# LEDDisp8.net
KiCad netlist of a schematic drawn in EAGLE
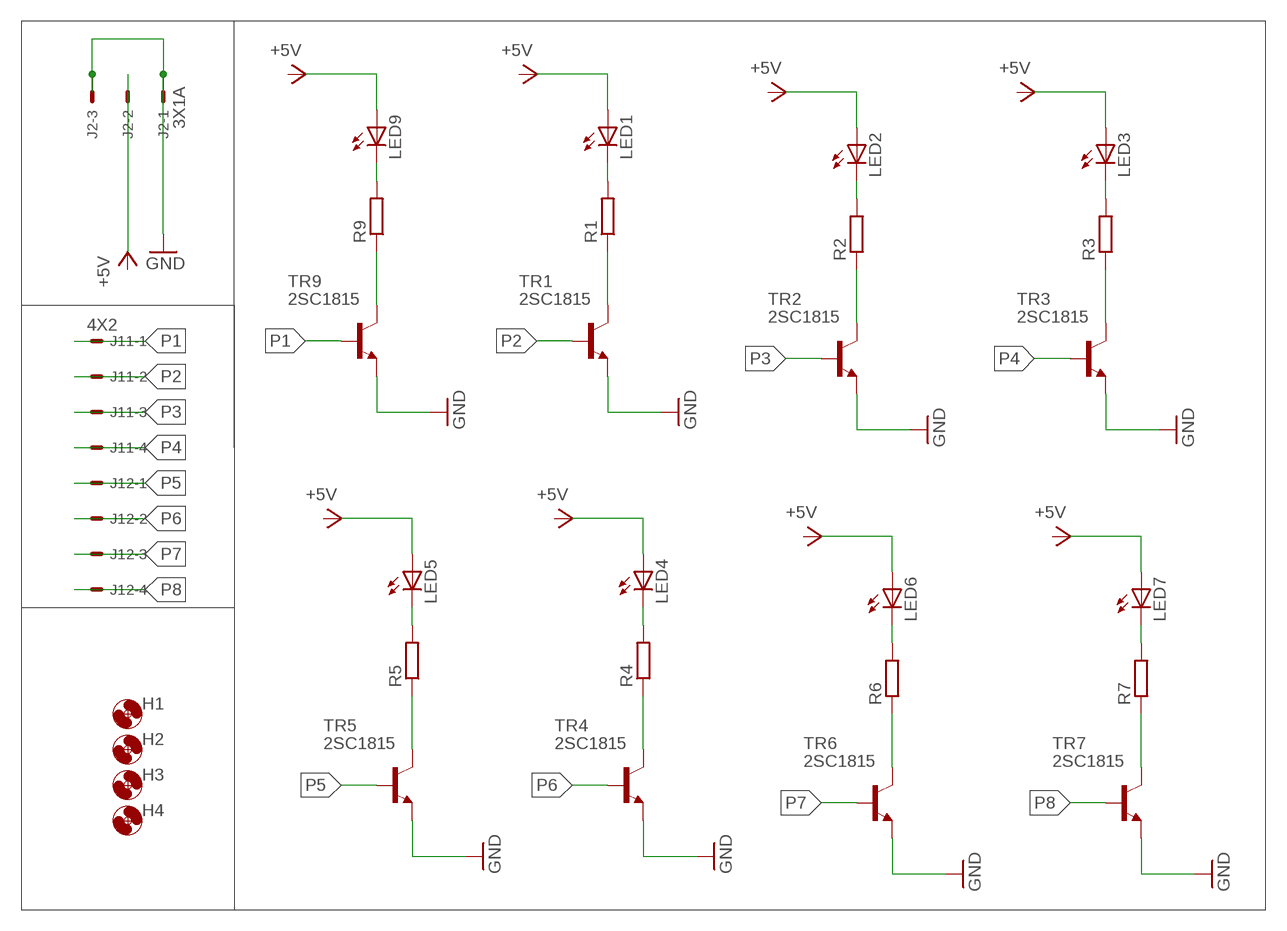
[diagram p0: schematic, sheet 1]

(export (version "E")
  (design (tool "Eeschema 10.0.6"))
  (components
    (comp (ref "H1")
      (value "HOLE3.3M3BOLT")
      (footprint "eagle-import:HOLE3.3")
      (libsource (lib "eagle-import") (part "HOLE3.3M3BOLT"))
    )
    (comp (ref "H2")
      (value "HOLE3.3M3BOLT")
      (footprint "eagle-import:HOLE3.3")
      (libsource (lib "eagle-import") (part "HOLE3.3M3BOLT"))
    )
    (comp (ref "H3")
      (value "HOLE3.3M3BOLT")
      (footprint "eagle-import:HOLE3.3")
      (libsource (lib "eagle-import") (part "HOLE3.3M3BOLT"))
    )
    (comp (ref "H4")
      (value "HOLE3.3M3BOLT")
      (footprint "eagle-import:HOLE3.3")
      (libsource (lib "eagle-import") (part "HOLE3.3M3BOLT"))
    )
    (comp (ref "J1")
      (value "4X2")
      (footprint "eagle-import:37208-62A3-004")
      (libsource (lib "eagle-import") (part "4X2"))
    )
    (comp (ref "J2")
      (value "3X1A")
      (footprint "eagle-import:37203-62A3-003")
      (libsource (lib "eagle-import") (part "3X1A"))
    )
    (comp (ref "LED1")
      (value "LED3MM")
      (footprint "eagle-import:LED3MM")
      (libsource (lib "eagle-import") (part "LED3MM"))
    )
    (comp (ref "LED2")
      (value "LED3MM")
      (footprint "eagle-import:LED3MM")
      (libsource (lib "eagle-import") (part "LED3MM"))
    )
    (comp (ref "LED3")
      (value "LED3MM")
      (footprint "eagle-import:LED3MM")
      (libsource (lib "eagle-import") (part "LED3MM"))
    )
    (comp (ref "LED4")
      (value "LED3MM")
      (footprint "eagle-import:LED3MM")
      (libsource (lib "eagle-import") (part "LED3MM"))
    )
    (comp (ref "LED5")
      (value "LED3MM")
      (footprint "eagle-import:LED3MM")
      (libsource (lib "eagle-import") (part "LED3MM"))
    )
    (comp (ref "LED6")
      (value "LED3MM")
      (footprint "eagle-import:LED3MM")
      (libsource (lib "eagle-import") (part "LED3MM"))
    )
    (comp (ref "LED7")
      (value "LED3MM")
      (footprint "eagle-import:LED3MM")
      (libsource (lib "eagle-import") (part "LED3MM"))
    )
    (comp (ref "LED9")
      (value "LED3MM")
      (footprint "eagle-import:LED3MM")
      (libsource (lib "eagle-import") (part "LED3MM"))
    )
    (comp (ref "R1")
      (value "R-EU_R3216W")
      (footprint "eagle-import:R3216W")
      (libsource (lib "eagle-import") (part "R-EU_R3216W"))
    )
    (comp (ref "R2")
      (value "R-EU_R3216W")
      (footprint "eagle-import:R3216W")
      (libsource (lib "eagle-import") (part "R-EU_R3216W"))
    )
    (comp (ref "R3")
      (value "R-EU_R3216W")
      (footprint "eagle-import:R3216W")
      (libsource (lib "eagle-import") (part "R-EU_R3216W"))
    )
    (comp (ref "R4")
      (value "R-EU_R3216W")
      (footprint "eagle-import:R3216W")
      (libsource (lib "eagle-import") (part "R-EU_R3216W"))
    )
    (comp (ref "R5")
      (value "R-EU_R3216W")
      (footprint "eagle-import:R3216W")
      (libsource (lib "eagle-import") (part "R-EU_R3216W"))
    )
    (comp (ref "R6")
      (value "R-EU_R3216W")
      (footprint "eagle-import:R3216W")
      (libsource (lib "eagle-import") (part "R-EU_R3216W"))
    )
    (comp (ref "R7")
      (value "R-EU_R3216W")
      (footprint "eagle-import:R3216W")
      (libsource (lib "eagle-import") (part "R-EU_R3216W"))
    )
    (comp (ref "R9")
      (value "R-EU_R3216W")
      (footprint "eagle-import:R3216W")
      (libsource (lib "eagle-import") (part "R-EU_R3216W"))
    )
    (comp (ref "TR1")
      (value "2SC1815")
      (footprint "eagle-import:TO92-")
      (libsource (lib "eagle-import") (part "2SC1815"))
    )
    (comp (ref "TR2")
      (value "2SC1815")
      (footprint "eagle-import:TO92-")
      (libsource (lib "eagle-import") (part "2SC1815"))
    )
    (comp (ref "TR3")
      (value "2SC1815")
      (footprint "eagle-import:TO92-")
      (libsource (lib "eagle-import") (part "2SC1815"))
    )
    (comp (ref "TR4")
      (value "2SC1815")
      (footprint "eagle-import:TO92-")
      (libsource (lib "eagle-import") (part "2SC1815"))
    )
    (comp (ref "TR5")
      (value "2SC1815")
      (footprint "eagle-import:TO92-")
      (libsource (lib "eagle-import") (part "2SC1815"))
    )
    (comp (ref "TR6")
      (value "2SC1815")
      (footprint "eagle-import:TO92-")
      (libsource (lib "eagle-import") (part "2SC1815"))
    )
    (comp (ref "TR7")
      (value "2SC1815")
      (footprint "eagle-import:TO92-")
      (libsource (lib "eagle-import") (part "2SC1815"))
    )
    (comp (ref "TR9")
      (value "2SC1815")
      (footprint "eagle-import:TO92-")
      (libsource (lib "eagle-import") (part "2SC1815"))
    )
  )
  (nets
    (net (code "2") (name "GND") (class "Default")
      (node (ref "J2") (pin "1-1") (pinfunction "S_1-1") (pintype "passive"))
      (node (ref "J2") (pin "1-3") (pinfunction "S_1-3") (pintype "passive"))
      (node (ref "TR1") (pin "E") (pinfunction "E_E") (pintype "passive"))
      (node (ref "TR2") (pin "E") (pinfunction "E_E") (pintype "passive"))
      (node (ref "TR3") (pin "E") (pinfunction "E_E") (pintype "passive"))
      (node (ref "TR4") (pin "E") (pinfunction "E_E") (pintype "passive"))
      (node (ref "TR5") (pin "E") (pinfunction "E_E") (pintype "passive"))
      (node (ref "TR6") (pin "E") (pinfunction "E_E") (pintype "passive"))
      (node (ref "TR7") (pin "E") (pinfunction "E_E") (pintype "passive"))
      (node (ref "TR9") (pin "E") (pinfunction "E_E") (pintype "passive"))
    )
    (net (code "3") (name "Net-(LED1-C)") (class "Default")
      (node (ref "LED1") (pin "K") (pinfunction "C_K") (pintype "passive"))
      (node (ref "R1") (pin "2") (pinfunction "2_2") (pintype "passive"))
    )
    (net (code "4") (name "Net-(LED2-C)") (class "Default")
      (node (ref "LED2") (pin "K") (pinfunction "C_K") (pintype "passive"))
      (node (ref "R2") (pin "2") (pinfunction "2_2") (pintype "passive"))
    )
    (net (code "5") (name "Net-(LED3-C)") (class "Default")
      (node (ref "LED3") (pin "K") (pinfunction "C_K") (pintype "passive"))
      (node (ref "R3") (pin "2") (pinfunction "2_2") (pintype "passive"))
    )
    (net (code "6") (name "Net-(LED4-C)") (class "Default")
      (node (ref "LED4") (pin "K") (pinfunction "C_K") (pintype "passive"))
      (node (ref "R4") (pin "2") (pinfunction "2_2") (pintype "passive"))
    )
    (net (code "7") (name "Net-(LED5-C)") (class "Default")
      (node (ref "LED5") (pin "K") (pinfunction "C_K") (pintype "passive"))
      (node (ref "R5") (pin "2") (pinfunction "2_2") (pintype "passive"))
    )
    (net (code "8") (name "Net-(LED6-C)") (class "Default")
      (node (ref "LED6") (pin "K") (pinfunction "C_K") (pintype "passive"))
      (node (ref "R6") (pin "2") (pinfunction "2_2") (pintype "passive"))
    )
    (net (code "9") (name "Net-(LED7-C)") (class "Default")
      (node (ref "LED7") (pin "K") (pinfunction "C_K") (pintype "passive"))
      (node (ref "R7") (pin "2") (pinfunction "2_2") (pintype "passive"))
    )
    (net (code "10") (name "Net-(LED9-C)") (class "Default")
      (node (ref "LED9") (pin "K") (pinfunction "C_K") (pintype "passive"))
      (node (ref "R9") (pin "2") (pinfunction "2_2") (pintype "passive"))
    )
    (net (code "11") (name "Net-(R1-Pad1)") (class "Default")
      (node (ref "R1") (pin "1") (pinfunction "1_1") (pintype "passive"))
      (node (ref "TR1") (pin "C") (pinfunction "C_C") (pintype "passive"))
    )
    (net (code "12") (name "Net-(R2-Pad1)") (class "Default")
      (node (ref "R2") (pin "1") (pinfunction "1_1") (pintype "passive"))
      (node (ref "TR2") (pin "C") (pinfunction "C_C") (pintype "passive"))
    )
    (net (code "13") (name "Net-(R3-Pad1)") (class "Default")
      (node (ref "R3") (pin "1") (pinfunction "1_1") (pintype "passive"))
      (node (ref "TR3") (pin "C") (pinfunction "C_C") (pintype "passive"))
    )
    (net (code "14") (name "Net-(R4-Pad1)") (class "Default")
      (node (ref "R4") (pin "1") (pinfunction "1_1") (pintype "passive"))
      (node (ref "TR4") (pin "C") (pinfunction "C_C") (pintype "passive"))
    )
    (net (code "15") (name "Net-(R5-Pad1)") (class "Default")
      (node (ref "R5") (pin "1") (pinfunction "1_1") (pintype "passive"))
      (node (ref "TR5") (pin "C") (pinfunction "C_C") (pintype "passive"))
    )
    (net (code "16") (name "Net-(R6-Pad1)") (class "Default")
      (node (ref "R6") (pin "1") (pinfunction "1_1") (pintype "passive"))
      (node (ref "TR6") (pin "C") (pinfunction "C_C") (pintype "passive"))
    )
    (net (code "17") (name "Net-(R7-Pad1)") (class "Default")
      (node (ref "R7") (pin "1") (pinfunction "1_1") (pintype "passive"))
      (node (ref "TR7") (pin "C") (pinfunction "C_C") (pintype "passive"))
    )
    (net (code "18") (name "Net-(R9-Pad1)") (class "Default")
      (node (ref "R9") (pin "1") (pinfunction "1_1") (pintype "passive"))
      (node (ref "TR9") (pin "C") (pinfunction "C_C") (pintype "passive"))
    )
    (net (code "19") (name "P1") (class "Default")
      (node (ref "J1") (pin "1-1") (pinfunction "S_1-1") (pintype "passive"))
      (node (ref "TR9") (pin "B") (pinfunction "B_B") (pintype "passive"))
    )
    (net (code "20") (name "P2") (class "Default")
      (node (ref "J1") (pin "1-2") (pinfunction "S_1-2") (pintype "passive"))
      (node (ref "TR1") (pin "B") (pinfunction "B_B") (pintype "passive"))
    )
    (net (code "21") (name "P3") (class "Default")
      (node (ref "J1") (pin "1-3") (pinfunction "S_1-3") (pintype "passive"))
      (node (ref "TR2") (pin "B") (pinfunction "B_B") (pintype "passive"))
    )
    (net (code "22") (name "P4") (class "Default")
      (node (ref "J1") (pin "1-4") (pinfunction "S_1-4") (pintype "passive"))
      (node (ref "TR3") (pin "B") (pinfunction "B_B") (pintype "passive"))
    )
    (net (code "23") (name "P5") (class "Default")
      (node (ref "J1") (pin "2-1") (pinfunction "S_2-1") (pintype "passive"))
      (node (ref "TR5") (pin "B") (pinfunction "B_B") (pintype "passive"))
    )
    (net (code "24") (name "P6") (class "Default")
      (node (ref "J1") (pin "2-2") (pinfunction "S_2-2") (pintype "passive"))
      (node (ref "TR4") (pin "B") (pinfunction "B_B") (pintype "passive"))
    )
    (net (code "25") (name "P7") (class "Default")
      (node (ref "J1") (pin "2-3") (pinfunction "S_2-3") (pintype "passive"))
      (node (ref "TR6") (pin "B") (pinfunction "B_B") (pintype "passive"))
    )
    (net (code "26") (name "P8") (class "Default")
      (node (ref "J1") (pin "2-4") (pinfunction "S_2-4") (pintype "passive"))
      (node (ref "TR7") (pin "B") (pinfunction "B_B") (pintype "passive"))
    )
    (net (code "27") (name "unconnected-(J2B-S-Pad1-2)") (class "Default")
      (node (ref "J2") (pin "1-2") (pinfunction "S_1-2") (pintype "passive"))
    )
    (net (code "28") (name "unconnected-(LED1-PadA)") (class "Default")
      (node (ref "LED1") (pin "A") (pinfunction "A_A") (pintype "passive"))
    )
    (net (code "29") (name "unconnected-(LED2-PadA)") (class "Default")
      (node (ref "LED2") (pin "A") (pinfunction "A_A") (pintype "passive"))
    )
    (net (code "30") (name "unconnected-(LED3-PadA)") (class "Default")
      (node (ref "LED3") (pin "A") (pinfunction "A_A") (pintype "passive"))
    )
    (net (code "31") (name "unconnected-(LED4-PadA)") (class "Default")
      (node (ref "LED4") (pin "A") (pinfunction "A_A") (pintype "passive"))
    )
    (net (code "32") (name "unconnected-(LED5-PadA)") (class "Default")
      (node (ref "LED5") (pin "A") (pinfunction "A_A") (pintype "passive"))
    )
    (net (code "33") (name "unconnected-(LED6-PadA)") (class "Default")
      (node (ref "LED6") (pin "A") (pinfunction "A_A") (pintype "passive"))
    )
    (net (code "34") (name "unconnected-(LED7-PadA)") (class "Default")
      (node (ref "LED7") (pin "A") (pinfunction "A_A") (pintype "passive"))
    )
    (net (code "35") (name "unconnected-(LED9-PadA)") (class "Default")
      (node (ref "LED9") (pin "A") (pinfunction "A_A") (pintype "passive"))
    )
  )
)
